# Audio_board_1_1.net
KiCad netlist of a schematic drawn in EAGLE
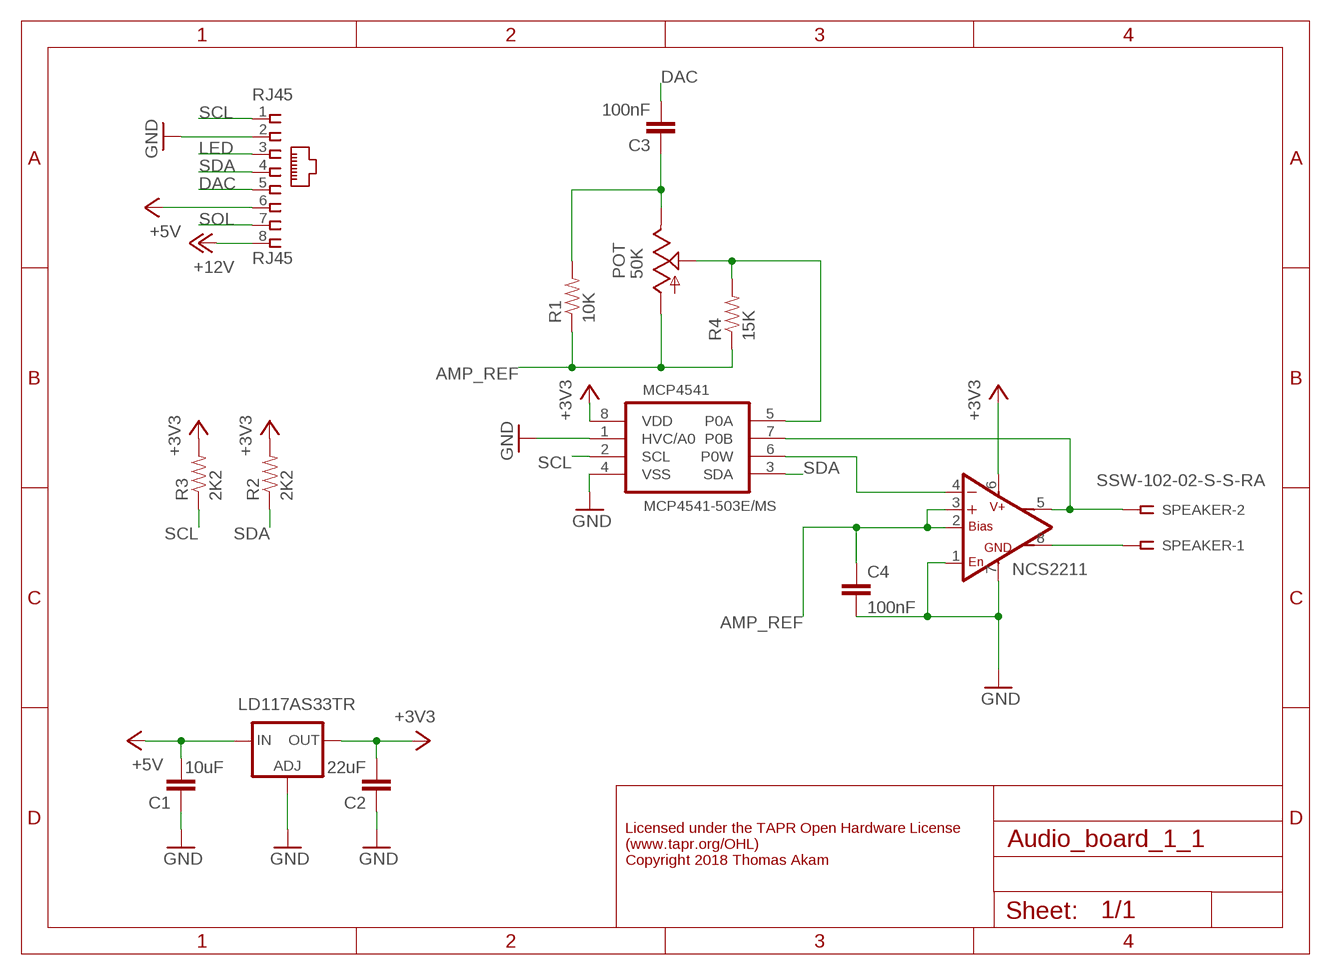
[diagram p0: schematic, sheet 1]

(export (version "E")
  (design (tool "Eeschema 10.0.6"))
  (components
    (comp (ref "C1")
      (value "10uF")
      (footprint "eagle-import:C1206")
      (libsource (lib "eagle-import") (part "C-EUC1206"))
    )
    (comp (ref "C2")
      (value "22uF")
      (footprint "eagle-import:C1206")
      (libsource (lib "eagle-import") (part "C-EUC1206"))
    )
    (comp (ref "C3")
      (value "100nF")
      (footprint "eagle-import:C0805")
      (libsource (lib "eagle-import") (part "C-EUC0805"))
    )
    (comp (ref "C4")
      (value "100nF")
      (footprint "eagle-import:C0805")
      (libsource (lib "eagle-import") (part "C-EUC0805"))
    )
    (comp (ref "LD117")
      (value "LD117AS33TR")
      (footprint "eagle-import:SOT223")
      (libsource (lib "eagle-import") (part "LD117A?S33TR"))
    )
    (comp (ref "MCP4541")
      (value "MCP4541-503E/MS")
      (footprint "eagle-import:SOP65P490X110-8N")
      (libsource (lib "eagle-import") (part "MCP4541-503E/MS"))
    )
    (comp (ref "NCS2211")
      (value "NCS22111M")
      (footprint "eagle-import:SO08")
      (libsource (lib "eagle-import") (part "NCS2211M1"))
    )
    (comp (ref "POT")
      (value "50K")
      (footprint "eagle-import:RS3")
      (libsource (lib "eagle-import") (part "TRIM_US-RS3"))
    )
    (comp (ref "R1")
      (value "10K")
      (footprint "eagle-import:0805")
      (libsource (lib "eagle-import") (part "0.3OHM-1/8W-1%(0805)"))
    )
    (comp (ref "R2")
      (value "2K2")
      (footprint "eagle-import:0805")
      (libsource (lib "eagle-import") (part "0.3OHM-1/8W-1%(0805)"))
    )
    (comp (ref "R3")
      (value "2K2")
      (footprint "eagle-import:0805")
      (libsource (lib "eagle-import") (part "0.3OHM-1/8W-1%(0805)"))
    )
    (comp (ref "R4")
      (value "15K")
      (footprint "eagle-import:0805")
      (libsource (lib "eagle-import") (part "0.3OHM-1/8W-1%(0805)"))
    )
    (comp (ref "RJ45")
      (value "RJ45")
      (footprint "eagle-import:RJ45-NO-SHIELD-VERTICAL")
      (libsource (lib "eagle-import") (part "RJ45VERTICAL"))
    )
    (comp (ref "SPEAKER")
      (value "SSW-102-02-S-S-RA")
      (footprint "eagle-import:SSW-102-02-S-S-RA")
      (libsource (lib "eagle-import") (part "SSW-102-02-S-S-RA"))
    )
  )
  (nets
    (net (code "1") (name "+3V3") (class "Default")
      (node (ref "C2") (pin "2") (pinfunction "2_2") (pintype "passive"))
      (node (ref "LD117") (pin "4") (pinfunction "OUT_4") (pintype "passive"))
      (node (ref "MCP4541") (pin "8") (pinfunction "VDD_8") (pintype "power_in"))
      (node (ref "NCS2211") (pin "6") (pinfunction "VS_6") (pintype "power_in"))
      (node (ref "R2") (pin "2") (pinfunction "2_2") (pintype "passive"))
      (node (ref "R3") (pin "2") (pinfunction "2_2") (pintype "passive"))
    )
    (net (code "2") (name "+5V") (class "Default")
      (node (ref "C1") (pin "2") (pinfunction "2_2") (pintype "passive"))
      (node (ref "LD117") (pin "3") (pinfunction "IN_3") (pintype "input"))
      (node (ref "RJ45") (pin "6") (pinfunction "6_6") (pintype "passive"))
    )
    (net (code "3") (name "+12V") (class "Default")
      (node (ref "RJ45") (pin "8") (pinfunction "8_8") (pintype "passive"))
    )
    (net (code "4") (name "/AMP_REF") (class "Default")
      (node (ref "C4") (pin "1") (pinfunction "1_1") (pintype "passive"))
      (node (ref "NCS2211") (pin "2") (pinfunction "BIAS_2") (pintype "passive"))
      (node (ref "NCS2211") (pin "3") (pinfunction "+IN_3") (pintype "input"))
      (node (ref "POT") (pin "A") (pinfunction "A_A") (pintype "passive"))
      (node (ref "R1") (pin "1") (pinfunction "1_1") (pintype "passive"))
      (node (ref "R4") (pin "1") (pinfunction "1_1") (pintype "passive"))
    )
    (net (code "5") (name "/DAC") (class "Default")
      (node (ref "C3") (pin "2") (pinfunction "2_2") (pintype "passive"))
      (node (ref "RJ45") (pin "5") (pinfunction "5_5") (pintype "passive"))
    )
    (net (code "6") (name "/LED") (class "Default")
      (node (ref "RJ45") (pin "3") (pinfunction "3_3") (pintype "passive"))
    )
    (net (code "7") (name "/SCL") (class "Default")
      (node (ref "MCP4541") (pin "2") (pinfunction "SCL_2") (pintype "input"))
      (node (ref "R3") (pin "1") (pinfunction "1_1") (pintype "passive"))
      (node (ref "RJ45") (pin "1") (pinfunction "1_1") (pintype "passive"))
    )
    (net (code "8") (name "/SDA") (class "Default")
      (node (ref "MCP4541") (pin "3") (pinfunction "SDA_3") (pintype "bidirectional"))
      (node (ref "R2") (pin "1") (pinfunction "1_1") (pintype "passive"))
      (node (ref "RJ45") (pin "4") (pinfunction "4_4") (pintype "passive"))
    )
    (net (code "9") (name "/SOL") (class "Default")
      (node (ref "RJ45") (pin "7") (pinfunction "7_7") (pintype "passive"))
    )
    (net (code "10") (name "GND") (class "Default")
      (node (ref "C1") (pin "1") (pinfunction "1_1") (pintype "passive"))
      (node (ref "C2") (pin "1") (pinfunction "1_1") (pintype "passive"))
      (node (ref "C4") (pin "2") (pinfunction "2_2") (pintype "passive"))
      (node (ref "LD117") (pin "1") (pinfunction "ADJ_1") (pintype "input"))
      (node (ref "MCP4541") (pin "1") (pinfunction "HVC/A0_1") (pintype "input"))
      (node (ref "MCP4541") (pin "4") (pinfunction "VSS_4") (pintype "power_in"))
      (node (ref "NCS2211") (pin "1") (pinfunction "ENABLE_1") (pintype "passive"))
      (node (ref "NCS2211") (pin "7") (pinfunction "GND_7") (pintype "power_in"))
      (node (ref "RJ45") (pin "2") (pinfunction "2_2") (pintype "passive"))
    )
    (net (code "11") (name "Net-(C3-Pad1)") (class "Default")
      (node (ref "C3") (pin "1") (pinfunction "1_1") (pintype "passive"))
      (node (ref "POT") (pin "E") (pinfunction "E_E") (pintype "passive"))
      (node (ref "R1") (pin "2") (pinfunction "2_2") (pintype "passive"))
    )
    (net (code "12") (name "Net-(MCP4541-P0A)") (class "Default")
      (node (ref "MCP4541") (pin "5") (pinfunction "P0A_5") (pintype "passive"))
      (node (ref "POT") (pin "S") (pinfunction "S_S") (pintype "passive"))
      (node (ref "R4") (pin "2") (pinfunction "2_2") (pintype "passive"))
    )
    (net (code "13") (name "Net-(MCP4541-P0B)") (class "Default")
      (node (ref "MCP4541") (pin "7") (pinfunction "P0B_7") (pintype "passive"))
      (node (ref "NCS2211") (pin "5") (pinfunction "+OUT_5") (pintype "passive"))
      (node (ref "SPEAKER") (pin "2") (pinfunction "1_2") (pintype "passive"))
    )
    (net (code "14") (name "Net-(MCP4541-P0W)") (class "Default")
      (node (ref "MCP4541") (pin "6") (pinfunction "P0W_6") (pintype "passive"))
      (node (ref "NCS2211") (pin "4") (pinfunction "-IN_4") (pintype "input"))
    )
    (net (code "15") (name "Net-(NCS2211--OUT)") (class "Default")
      (node (ref "NCS2211") (pin "8") (pinfunction "-OUT_8") (pintype "output"))
      (node (ref "SPEAKER") (pin "1") (pinfunction "1_1") (pintype "passive"))
    )
  )
)
